# 2PCB-Part2.net
KiCad netlist of a schematic drawn in EAGLE
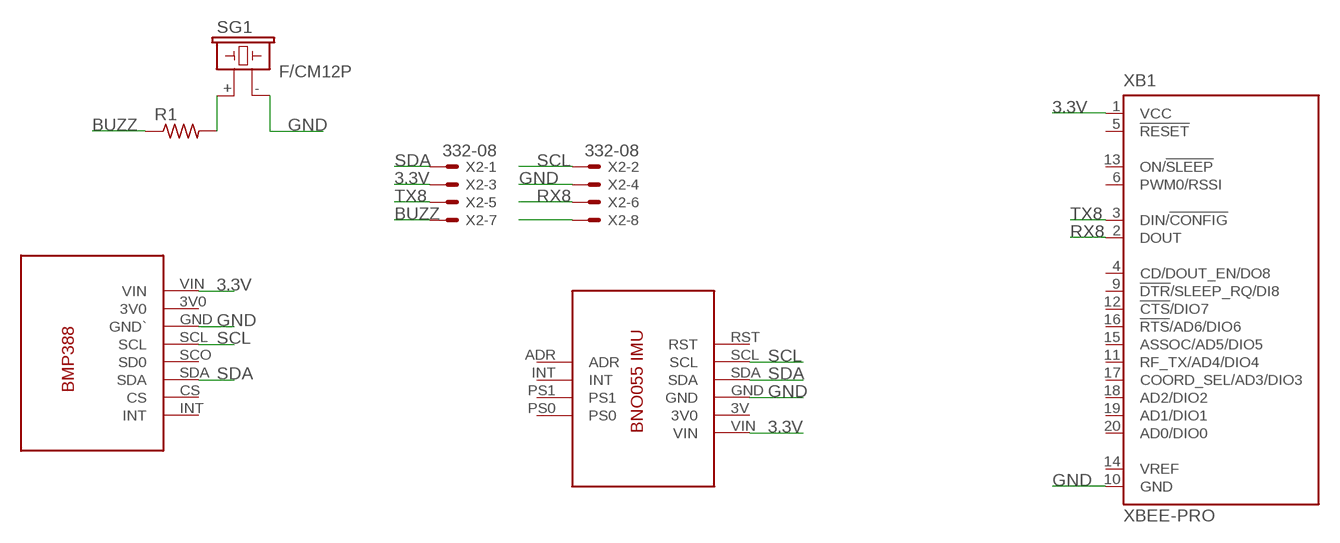
[diagram p0: schematic, sheet 1]

(export (version "E")
  (design (tool "Eeschema 10.0.6"))
  (components
    (comp (ref "R1")
      (value "R-US_0207/10")
      (footprint "eagle-import:0207_10")
      (libsource (lib "eagle-import") (part "R-US_0207/10"))
    )
    (comp (ref "SG1")
      (value "F/CM12P")
      (footprint "eagle-import:F_CM12P")
      (libsource (lib "eagle-import") (part "F/CM12P"))
    )
    (comp (ref "U$1")
      (value "BNO055")
      (footprint "eagle-import:BNO055")
      (libsource (lib "eagle-import") (part "BNO055"))
    )
    (comp (ref "U$2")
      (value "BMP388")
      (footprint "eagle-import:BMP388")
      (libsource (lib "eagle-import") (part "BMP388"))
    )
    (comp (ref "X2")
      (value "332-08")
      (footprint "eagle-import:332-08")
      (libsource (lib "eagle-import") (part "332-08"))
    )
    (comp (ref "XB1")
      (value "XBEE-PRO")
      (footprint "eagle-import:XBEE-PRO")
      (fields (field (name "MPN") "XBP24-AWI-001"))
      (libsource (lib "eagle-import") (part "XBEE-PRO"))
    )
  )
  (nets
    (net (code "1") (name "/3.3V") (class "Default")
      (node (ref "U$1") (pin "VIN") (pinfunction "VIN_VIN") (pintype "bidirectional"))
      (node (ref "U$2") (pin "VIN") (pinfunction "VIN_VIN") (pintype "bidirectional"))
      (node (ref "X2") (pin "3") (pinfunction "S_3") (pintype "passive"))
      (node (ref "XB1") (pin "1") (pinfunction "VCC_1") (pintype "power_in"))
    )
    (net (code "2") (name "/BUZZ") (class "Default")
      (node (ref "R1") (pin "1") (pinfunction "1_1") (pintype "passive"))
      (node (ref "X2") (pin "7") (pinfunction "S_7") (pintype "passive"))
    )
    (net (code "3") (name "/GND") (class "Default")
      (node (ref "SG1") (pin "-") (pinfunction "2_-") (pintype "passive"))
      (node (ref "U$1") (pin "GND") (pinfunction "GND_GND") (pintype "bidirectional"))
      (node (ref "U$2") (pin "GND") (pinfunction "GND`_GND") (pintype "bidirectional"))
      (node (ref "X2") (pin "4") (pinfunction "S_4") (pintype "passive"))
      (node (ref "XB1") (pin "10") (pinfunction "GND_10") (pintype "power_in"))
    )
    (net (code "4") (name "/RX8") (class "Default")
      (node (ref "X2") (pin "6") (pinfunction "S_6") (pintype "passive"))
      (node (ref "XB1") (pin "2") (pinfunction "DOUT_2") (pintype "output"))
    )
    (net (code "5") (name "/SCL") (class "Default")
      (node (ref "U$1") (pin "SCL") (pinfunction "SCL_SCL") (pintype "bidirectional"))
      (node (ref "U$2") (pin "SCL") (pinfunction "SCL_SCL") (pintype "bidirectional"))
      (node (ref "X2") (pin "2") (pinfunction "S_2") (pintype "passive"))
    )
    (net (code "6") (name "/SDA") (class "Default")
      (node (ref "U$1") (pin "SDA") (pinfunction "SDA_SDA") (pintype "bidirectional"))
      (node (ref "U$2") (pin "SDA") (pinfunction "SDA_SDA") (pintype "bidirectional"))
      (node (ref "X2") (pin "1") (pinfunction "S_1") (pintype "passive"))
    )
    (net (code "7") (name "/TX8") (class "Default")
      (node (ref "X2") (pin "5") (pinfunction "S_5") (pintype "passive"))
      (node (ref "XB1") (pin "3") (pinfunction "DIN/~{CONFIG}_3") (pintype "input"))
    )
    (net (code "8") (name "Net-(SG1-1)") (class "Default")
      (node (ref "R1") (pin "2") (pinfunction "2_2") (pintype "passive"))
      (node (ref "SG1") (pin "+") (pinfunction "1_+") (pintype "passive"))
    )
    (net (code "9") (name "unconnected-(U$1-3V0-Pad3V)") (class "Default")
      (node (ref "U$1") (pin "3V") (pinfunction "3V0_3V") (pintype "bidirectional"))
    )
    (net (code "10") (name "unconnected-(U$1-PadADR)") (class "Default")
      (node (ref "U$1") (pin "ADR") (pinfunction "ADR_ADR") (pintype "bidirectional"))
    )
    (net (code "11") (name "unconnected-(U$1-PadINT)") (class "Default")
      (node (ref "U$1") (pin "INT") (pinfunction "INT_INT") (pintype "bidirectional"))
    )
    (net (code "12") (name "unconnected-(U$1-PadPS0)") (class "Default")
      (node (ref "U$1") (pin "PS0") (pinfunction "PS0_PS0") (pintype "bidirectional"))
    )
    (net (code "13") (name "unconnected-(U$1-PadPS1)") (class "Default")
      (node (ref "U$1") (pin "PS1") (pinfunction "PS1_PS1") (pintype "bidirectional"))
    )
    (net (code "14") (name "unconnected-(U$1-PadRST)") (class "Default")
      (node (ref "U$1") (pin "RST") (pinfunction "RST_RST") (pintype "bidirectional"))
    )
    (net (code "15") (name "unconnected-(U$2-Pad3V0)") (class "Default")
      (node (ref "U$2") (pin "3V0") (pinfunction "3V0_3V0") (pintype "bidirectional"))
    )
    (net (code "16") (name "unconnected-(U$2-PadCS)") (class "Default")
      (node (ref "U$2") (pin "CS") (pinfunction "CS_CS") (pintype "bidirectional"))
    )
    (net (code "17") (name "unconnected-(U$2-PadINT)") (class "Default")
      (node (ref "U$2") (pin "INT") (pinfunction "INT_INT") (pintype "bidirectional"))
    )
    (net (code "18") (name "unconnected-(U$2-SD0-PadSCO)") (class "Default")
      (node (ref "U$2") (pin "SCO") (pinfunction "SD0_SCO") (pintype "bidirectional"))
    )
    (net (code "19") (name "unconnected-(X2H-S-Pad8)") (class "Default")
      (node (ref "X2") (pin "8") (pinfunction "S_8") (pintype "passive"))
    )
    (net (code "20") (name "unconnected-(XB1-AD0{slash}DIO0-Pad20)") (class "Default")
      (node (ref "XB1") (pin "20") (pinfunction "AD0/DIO0_20") (pintype "bidirectional"))
    )
    (net (code "21") (name "unconnected-(XB1-AD1{slash}DIO1-Pad19)") (class "Default")
      (node (ref "XB1") (pin "19") (pinfunction "AD1/DIO1_19") (pintype "bidirectional"))
    )
    (net (code "22") (name "unconnected-(XB1-AD2{slash}DIO2-Pad18)") (class "Default")
      (node (ref "XB1") (pin "18") (pinfunction "AD2/DIO2_18") (pintype "bidirectional"))
    )
    (net (code "23") (name "unconnected-(XB1-ASSOC{slash}AD5{slash}DIO5-Pad15)") (class "Default")
      (node (ref "XB1") (pin "15") (pinfunction "ASSOC/AD5/DIO5_15") (pintype "bidirectional"))
    )
    (net (code "24") (name "unconnected-(XB1-CD{slash}DOUT_EN{slash}DO8-Pad4)") (class "Default")
      (node (ref "XB1") (pin "4") (pinfunction "CD/DOUT_EN/DO8_4") (pintype "output"))
    )
    (net (code "25") (name "unconnected-(XB1-COORD_SEL{slash}AD3{slash}DIO3-Pad17)") (class "Default")
      (node (ref "XB1") (pin "17") (pinfunction "COORD_SEL/AD3/DIO3_17") (pintype "bidirectional"))
    )
    (net (code "26") (name "unconnected-(XB1-ON{slash}~{SLEEP}-Pad13)") (class "Default")
      (node (ref "XB1") (pin "13") (pinfunction "ON/~{SLEEP}_13") (pintype "output"))
    )
    (net (code "27") (name "unconnected-(XB1-PWM0{slash}RSSI-Pad6)") (class "Default")
      (node (ref "XB1") (pin "6") (pinfunction "PWM0/RSSI_6") (pintype "output"))
    )
    (net (code "28") (name "unconnected-(XB1-RF_TX{slash}AD4{slash}DIO4-Pad11)") (class "Default")
      (node (ref "XB1") (pin "11") (pinfunction "RF_TX/AD4/DIO4_11") (pintype "bidirectional"))
    )
    (net (code "29") (name "unconnected-(XB1-VREF-Pad14)") (class "Default")
      (node (ref "XB1") (pin "14") (pinfunction "VREF_14") (pintype "input"))
    )
    (net (code "30") (name "unconnected-(XB1-~{CTS}{slash}DIO7-Pad12)") (class "Default")
      (node (ref "XB1") (pin "12") (pinfunction "~{CTS}/DIO7_12") (pintype "bidirectional"))
    )
    (net (code "31") (name "unconnected-(XB1-~{DTR}{slash}SLEEP_RQ{slash}DI8-Pad9)") (class "Default")
      (node (ref "XB1") (pin "9") (pinfunction "~{DTR}/SLEEP_RQ/DI8_9") (pintype "bidirectional"))
    )
    (net (code "32") (name "unconnected-(XB1-~{RESET}-Pad5)") (class "Default")
      (node (ref "XB1") (pin "5") (pinfunction "~{RESET}_5") (pintype "input"))
    )
    (net (code "33") (name "unconnected-(XB1-~{RTS}{slash}AD6{slash}DIO6-Pad16)") (class "Default")
      (node (ref "XB1") (pin "16") (pinfunction "~{RTS}/AD6/DIO6_16") (pintype "bidirectional"))
    )
  )
)
